# BatteryHolder.net
KiCad netlist of a schematic drawn in Altium Designer
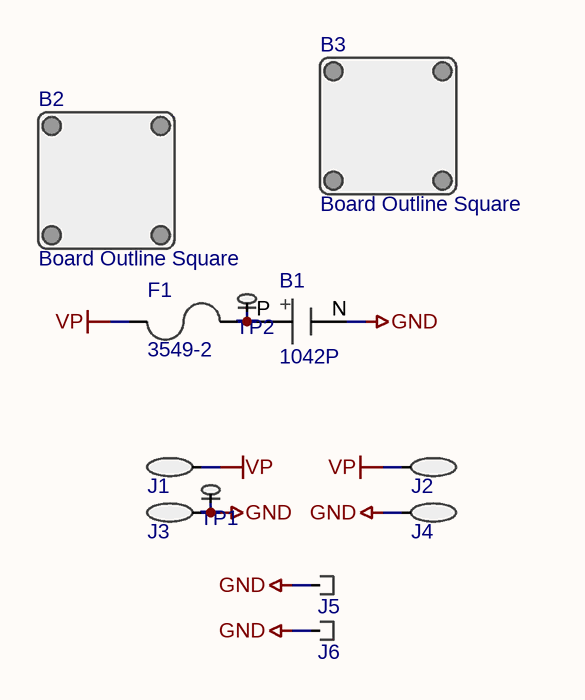
[diagram p0: BatteryHolder.SchDoc]

(export (version "E")
  (design (tool "Eeschema 10.0.6"))
  (components
    (comp (ref "B1")
      (value "1042P")
      (footprint "BATTERY_HOLDER_KEYSTONE_1042P")
      (libsource (lib "EE490") (part "Battery - Holder - Keystone 1042P"))
    )
    (comp (ref "B2")
      (value "Board Outline Square")
      (footprint "PCB_OUTLINE_SQUARE")
      (libsource (lib "EE490") (part "Board_Outline_Square"))
    )
    (comp (ref "B3")
      (value "Board Outline Square")
      (footprint "PCB_OUTLINE_SQUARE")
      (libsource (lib "EE490") (part "Board_Outline_Square"))
    )
    (comp (ref "F1")
      (value "3549-2")
      (footprint "FUSE_HOLDER_KEYSTONE_3549-2")
      (libsource (lib "EE490") (part "Fuse - Holder - Keystone 3549-2"))
    )
    (comp (ref "J1")
      (value "PP45")
      (footprint "CONNECTOR_BTOC_PP45_ANDERSON")
      (libsource (lib "EE490") (part "Connector - Modular - 1P - Anderson PP45"))
    )
    (comp (ref "J2")
      (value "PP45")
      (footprint "CONNECTOR_BTOC_PP45_ANDERSON")
      (libsource (lib "EE490") (part "Connector - Modular - 1P - Anderson PP45"))
    )
    (comp (ref "J3")
      (value "PP45")
      (footprint "CONNECTOR_BTOC_PP45_ANDERSON")
      (libsource (lib "EE490") (part "Connector - Modular - 1P - Anderson PP45"))
    )
    (comp (ref "J4")
      (value "PP45")
      (footprint "CONNECTOR_BTOC_PP45_ANDERSON")
      (libsource (lib "EE490") (part "Connector - Modular - 1P - Anderson PP45"))
    )
    (comp (ref "J5")
      (value "PP45 Staple")
      (footprint "CONNECTOR_ACCESSORY_PP45-STAPLE_ANDERSON")
      (libsource (lib "EE490") (part "Connector - Accessory - Mechanical Support - Anderson PP45 Staple"))
    )
    (comp (ref "J6")
      (value "PP45 Staple")
      (footprint "CONNECTOR_ACCESSORY_PP45-STAPLE_ANDERSON")
      (libsource (lib "EE490") (part "Connector - Accessory - Mechanical Support - Anderson PP45 Staple"))
    )
    (comp (ref "TP1")
      (value "519XTR")
      (footprint "TESTPOINT_LOOP_SMD_KEYSTONE_519X")
      (libsource (lib "EE490") (part "Test Point - SMT - Loop - Keystone 519X"))
    )
    (comp (ref "TP2")
      (value "519XTR")
      (footprint "TESTPOINT_LOOP_SMD_KEYSTONE_519X")
      (libsource (lib "EE490") (part "Test Point - SMT - Loop - Keystone 519X"))
    )
  )
  (nets
    (net (code "1") (name "GND") (class "Default")
      (node (ref "B1") (pin "N") (pinfunction "N_N") (pintype "passive"))
      (node (ref "J3") (pin "1") (pinfunction "1_1") (pintype "passive"))
      (node (ref "J4") (pin "1") (pinfunction "1_1") (pintype "passive"))
      (node (ref "J5") (pin "1") (pinfunction "1_1") (pintype "passive"))
      (node (ref "J6") (pin "1") (pinfunction "1_1") (pintype "passive"))
      (node (ref "TP1") (pin "1") (pinfunction "1_1") (pintype "passive"))
    )
    (net (code "2") (name "Net-(B1-PadP)") (class "Default")
      (node (ref "B1") (pin "P") (pinfunction "P_P") (pintype "passive"))
      (node (ref "F1") (pin "1") (pinfunction "1_1") (pintype "passive"))
      (node (ref "TP2") (pin "1") (pinfunction "1_1") (pintype "passive"))
    )
    (net (code "3") (name "VP") (class "Default")
      (node (ref "F1") (pin "2") (pinfunction "2_2") (pintype "passive"))
      (node (ref "J1") (pin "1") (pinfunction "1_1") (pintype "passive"))
      (node (ref "J2") (pin "1") (pinfunction "1_1") (pintype "passive"))
    )
  )
)
